# SWM341_DAPLink_2T45.net
KiCad netlist of a schematic drawn in EasyEDA
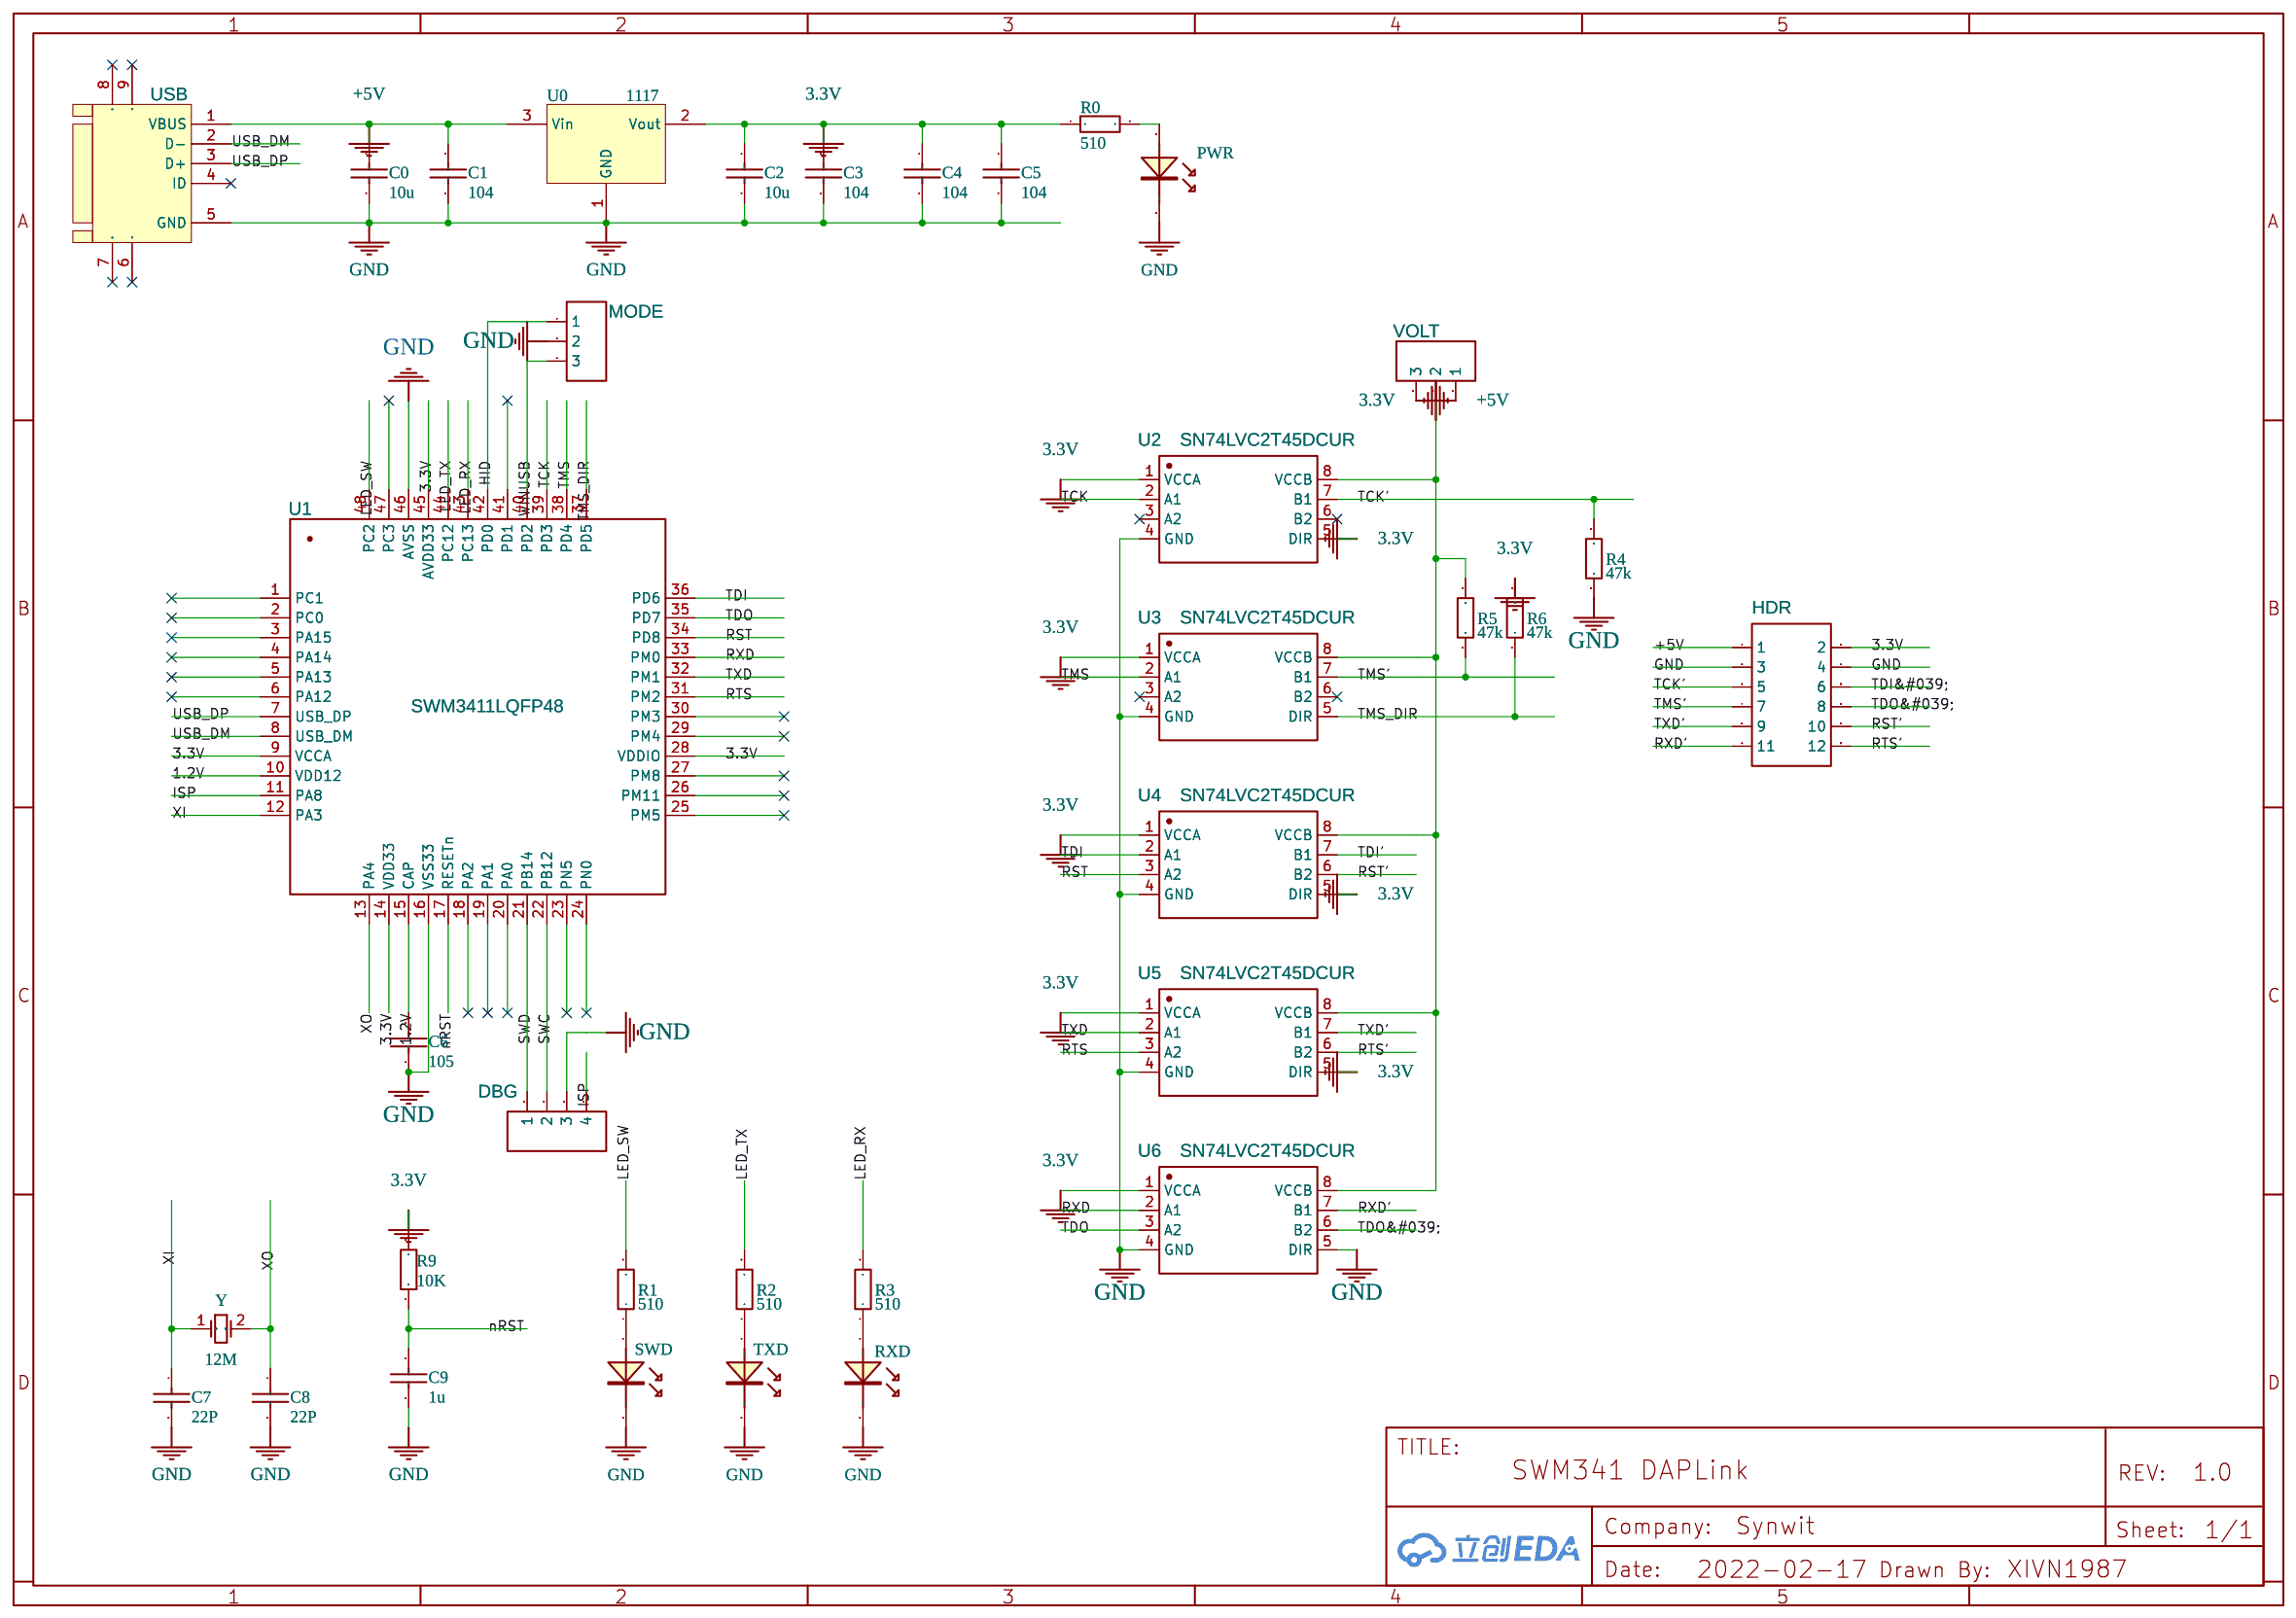
[diagram p0: schematic sheet]

(export (version "E")
  (design (tool "Eeschema 10.0.6"))
  (components
    (comp (ref "C0") (value "10u") (libsource (lib "") (part "Unknown_180_-740")))
    (comp (ref "C1") (value "104") (libsource (lib "") (part "Unknown_220_-740")))
    (comp (ref "C2") (value "10u") (libsource (lib "") (part "Unknown_370_-740")))
    (comp (ref "C3") (value "104") (libsource (lib "") (part "Unknown_410_-740")))
    (comp (ref "C4") (value "104") (libsource (lib "") (part "Unknown_460_-740")))
    (comp (ref "C5") (value "104") (libsource (lib "") (part "Unknown_500_-740")))
    (comp (ref "C6") (value "105") (libsource (lib "") (part "Unknown_200_-300")))
    (comp (ref "C7") (value "22P") (libsource (lib "") (part "Unknown_80_-120")))
    (comp (ref "C8") (value "22P") (libsource (lib "") (part "Unknown_130_-120")))
    (comp (ref "C9") (value "1u") (libsource (lib "") (part "Unknown_200_-130")))
    (comp (ref "DBG")
      (value "HDR-M-2.54_1x4")
      (fields (field (name "BOM_Supplier Part") "C124378"))
      (libsource (lib "") (part "HDR-M-2.54_1x4"))
    )
    (comp (ref "HDR")
      (value "HDR-M-2.54_2x6")
      (fields (field (name "BOM_Supplier Part") "C124388"))
      (libsource (lib "") (part "HDR-M-2.54_2x6"))
    )
    (comp (ref "MODE")
      (value "HDR-M-2.54_1x3")
      (fields (field (name "BOM_Supplier Part") "C180248"))
      (libsource (lib "") (part "HDR-M-2.54_1x3_1"))
    )
    (comp (ref "PWR") (value "NO") (libsource (lib "") (part "Unknown_580_-750")))
    (comp (ref "R0") (value "510") (libsource (lib "") (part "Unknown_560_-750")))
    (comp (ref "R1") (value "510") (libsource (lib "") (part "Unknown_310_-170")))
    (comp (ref "R2") (value "510") (libsource (lib "") (part "Unknown_370_-170")))
    (comp (ref "R3") (value "510") (libsource (lib "") (part "Unknown_430_-170")))
    (comp (ref "R4") (value "47k") (libsource (lib "") (part "Unknown_800_-540")))
    (comp (ref "R5") (value "47k") (libsource (lib "") (part "Unknown_735_-510")))
    (comp (ref "R6") (value "47k") (libsource (lib "") (part "Unknown_760_-510")))
    (comp (ref "R9") (value "10K") (libsource (lib "") (part "Unknown_200_-180")))
    (comp (ref "RXD") (value "NO") (libsource (lib "") (part "Unknown_430_-140")))
    (comp (ref "SWD") (value "NO") (libsource (lib "") (part "Unknown_310_-140")))
    (comp (ref "TXD") (value "NO") (libsource (lib "") (part "Unknown_370_-140")))
    (comp (ref "U0") (value "1117") (libsource (lib "") (part "Unknown_330_-720")))
    (comp (ref "U1") (value "SWM3411LQFP48") (libsource (lib "") (part "SWM3411LQFP48")))
    (comp (ref "U2")
      (value "SN74LVC2T45DCUR")
      (fields (field (name "BOM_Supplier Part") "C15741"))
      (libsource (lib "") (part "SN74LVC2T45DCUR"))
    )
    (comp (ref "U3")
      (value "SN74LVC2T45DCUR")
      (fields (field (name "BOM_Supplier Part") "C15741"))
      (libsource (lib "") (part "SN74LVC2T45DCUR"))
    )
    (comp (ref "U4")
      (value "SN74LVC2T45DCUR")
      (fields (field (name "BOM_Supplier Part") "C15741"))
      (libsource (lib "") (part "SN74LVC2T45DCUR"))
    )
    (comp (ref "U5")
      (value "SN74LVC2T45DCUR")
      (fields (field (name "BOM_Supplier Part") "C15741"))
      (libsource (lib "") (part "SN74LVC2T45DCUR"))
    )
    (comp (ref "U6")
      (value "SN74LVC2T45DCUR")
      (fields (field (name "BOM_Supplier Part") "C15741"))
      (libsource (lib "") (part "SN74LVC2T45DCUR"))
    )
    (comp (ref "USB") (value "MicroUSB") (libsource (lib "") (part "MicroUSB")))
    (comp (ref "VOLT")
      (value "HDR-M-2.54_1x3")
      (fields (field (name "BOM_Supplier Part") "C180248"))
      (libsource (lib "") (part "HDR-M-2.54_1x3"))
    )
    (comp (ref "Y") (value "12M") (libsource (lib "") (part "Unknown_100_-140")))
  )
  (nets
    (net (code "1") (name "+5V") (class "Default")
      (node (ref "C0") (pin "1") (pinfunction "1_1") (pintype "unspecified"))
      (node (ref "C1") (pin "1") (pinfunction "1_1") (pintype "unspecified"))
      (node (ref "HDR") (pin "1") (pinfunction "1_1") (pintype "unspecified"))
      (node (ref "U0") (pin "3") (pinfunction "Vin_3") (pintype "unspecified"))
      (node (ref "USB") (pin "1") (pinfunction "VBUS_1") (pintype "unspecified"))
      (node (ref "VOLT") (pin "1") (pinfunction "1_1") (pintype "input"))
    )
    (net (code "2") (name "/1.2V") (class "Default")
      (node (ref "C6") (pin "1") (pinfunction "1_1") (pintype "unspecified"))
      (node (ref "U1") (pin "10") (pinfunction "VDD12_10") (pintype "unspecified"))
      (node (ref "U1") (pin "15") (pinfunction "CAP_15") (pintype "unspecified"))
    )
    (net (code "3") (name "/HID") (class "Default")
      (node (ref "MODE") (pin "1") (pinfunction "1_1") (pintype "input"))
      (node (ref "U1") (pin "42") (pinfunction "PD0_42") (pintype "unspecified"))
    )
    (net (code "4") (name "/ISP") (class "Default")
      (node (ref "DBG") (pin "4") (pinfunction "4_4") (pintype "unspecified"))
      (node (ref "U1") (pin "11") (pinfunction "PA8_11") (pintype "unspecified"))
    )
    (net (code "5") (name "/LED_RX") (class "Default")
      (node (ref "R3") (pin "2") (pinfunction "2_2") (pintype "unspecified"))
      (node (ref "U1") (pin "43") (pinfunction "PC13_43") (pintype "unspecified"))
    )
    (net (code "6") (name "/LED_SW") (class "Default")
      (node (ref "R1") (pin "2") (pinfunction "2_2") (pintype "unspecified"))
      (node (ref "U1") (pin "48") (pinfunction "PC2_48") (pintype "unspecified"))
    )
    (net (code "7") (name "/LED_TX") (class "Default")
      (node (ref "R2") (pin "2") (pinfunction "2_2") (pintype "unspecified"))
      (node (ref "U1") (pin "44") (pinfunction "PC12_44") (pintype "unspecified"))
    )
    (net (code "8") (name "/RST") (class "Default")
      (node (ref "U1") (pin "34") (pinfunction "PD8_34") (pintype "unspecified"))
      (node (ref "U4") (pin "3") (pinfunction "A2_3") (pintype "unspecified"))
    )
    (net (code "9") (name "/RST'") (class "Default")
      (node (ref "HDR") (pin "10") (pinfunction "10_10") (pintype "unspecified"))
      (node (ref "U4") (pin "6") (pinfunction "B2_6") (pintype "unspecified"))
    )
    (net (code "10") (name "/RTS") (class "Default")
      (node (ref "U1") (pin "31") (pinfunction "PM2_31") (pintype "unspecified"))
      (node (ref "U5") (pin "3") (pinfunction "A2_3") (pintype "unspecified"))
    )
    (net (code "11") (name "/RTS'") (class "Default")
      (node (ref "HDR") (pin "12") (pinfunction "12_12") (pintype "unspecified"))
      (node (ref "U5") (pin "6") (pinfunction "B2_6") (pintype "unspecified"))
    )
    (net (code "12") (name "/RXD") (class "Default")
      (node (ref "U1") (pin "33") (pinfunction "PM0_33") (pintype "unspecified"))
      (node (ref "U6") (pin "2") (pinfunction "A1_2") (pintype "unspecified"))
    )
    (net (code "13") (name "/RXD'") (class "Default")
      (node (ref "HDR") (pin "11") (pinfunction "11_11") (pintype "unspecified"))
      (node (ref "U6") (pin "7") (pinfunction "B1_7") (pintype "unspecified"))
    )
    (net (code "14") (name "/SWC") (class "Default")
      (node (ref "DBG") (pin "2") (pinfunction "2_2") (pintype "unspecified"))
      (node (ref "U1") (pin "22") (pinfunction "PB12_22") (pintype "unspecified"))
    )
    (net (code "15") (name "/SWD") (class "Default")
      (node (ref "DBG") (pin "1") (pinfunction "1_1") (pintype "unspecified"))
      (node (ref "U1") (pin "21") (pinfunction "PB14_21") (pintype "unspecified"))
    )
    (net (code "16") (name "/TCK") (class "Default")
      (node (ref "U1") (pin "39") (pinfunction "PD3_39") (pintype "unspecified"))
      (node (ref "U2") (pin "2") (pinfunction "A1_2") (pintype "unspecified"))
    )
    (net (code "17") (name "/TCK'") (class "Default")
      (node (ref "HDR") (pin "5") (pinfunction "5_5") (pintype "unspecified"))
      (node (ref "R4") (pin "2") (pinfunction "2_2") (pintype "unspecified"))
      (node (ref "U2") (pin "7") (pinfunction "B1_7") (pintype "unspecified"))
    )
    (net (code "18") (name "/TDI") (class "Default")
      (node (ref "U1") (pin "36") (pinfunction "PD6_36") (pintype "unspecified"))
      (node (ref "U4") (pin "2") (pinfunction "A1_2") (pintype "unspecified"))
    )
    (net (code "19") (name "/TDI&#039;") (class "Default")
      (node (ref "HDR") (pin "6") (pinfunction "6_6") (pintype "unspecified"))
    )
    (net (code "20") (name "/TDI'") (class "Default")
      (node (ref "U4") (pin "7") (pinfunction "B1_7") (pintype "unspecified"))
    )
    (net (code "21") (name "/TDO") (class "Default")
      (node (ref "U1") (pin "35") (pinfunction "PD7_35") (pintype "unspecified"))
      (node (ref "U6") (pin "3") (pinfunction "A2_3") (pintype "unspecified"))
    )
    (net (code "22") (name "/TDO&#039;") (class "Default")
      (node (ref "HDR") (pin "8") (pinfunction "8_8") (pintype "unspecified"))
      (node (ref "U6") (pin "6") (pinfunction "B2_6") (pintype "unspecified"))
    )
    (net (code "23") (name "/TMS") (class "Default")
      (node (ref "U1") (pin "38") (pinfunction "PD4_38") (pintype "unspecified"))
      (node (ref "U3") (pin "2") (pinfunction "A1_2") (pintype "unspecified"))
    )
    (net (code "24") (name "/TMS'") (class "Default")
      (node (ref "HDR") (pin "7") (pinfunction "7_7") (pintype "unspecified"))
      (node (ref "R5") (pin "1") (pinfunction "1_1") (pintype "unspecified"))
      (node (ref "U3") (pin "7") (pinfunction "B1_7") (pintype "unspecified"))
    )
    (net (code "25") (name "/TMS_DIR") (class "Default")
      (node (ref "R6") (pin "1") (pinfunction "1_1") (pintype "unspecified"))
      (node (ref "U1") (pin "37") (pinfunction "PD5_37") (pintype "unspecified"))
      (node (ref "U3") (pin "5") (pinfunction "DIR_5") (pintype "unspecified"))
    )
    (net (code "26") (name "/TXD") (class "Default")
      (node (ref "U1") (pin "32") (pinfunction "PM1_32") (pintype "unspecified"))
      (node (ref "U5") (pin "2") (pinfunction "A1_2") (pintype "unspecified"))
    )
    (net (code "27") (name "/TXD'") (class "Default")
      (node (ref "HDR") (pin "9") (pinfunction "9_9") (pintype "unspecified"))
      (node (ref "U5") (pin "7") (pinfunction "B1_7") (pintype "unspecified"))
    )
    (net (code "28") (name "/USB_DM") (class "Default")
      (node (ref "U1") (pin "8") (pinfunction "USB_DM_8") (pintype "unspecified"))
      (node (ref "USB") (pin "2") (pinfunction "D-_2") (pintype "unspecified"))
    )
    (net (code "29") (name "/USB_DP") (class "Default")
      (node (ref "U1") (pin "7") (pinfunction "USB_DP_7") (pintype "unspecified"))
      (node (ref "USB") (pin "3") (pinfunction "D+_3") (pintype "unspecified"))
    )
    (net (code "30") (name "/WINUSB") (class "Default")
      (node (ref "MODE") (pin "3") (pinfunction "3_3") (pintype "input"))
      (node (ref "U1") (pin "40") (pinfunction "PD2_40") (pintype "unspecified"))
    )
    (net (code "31") (name "/XI") (class "Default")
      (node (ref "C7") (pin "1") (pinfunction "1_1") (pintype "unspecified"))
      (node (ref "U1") (pin "12") (pinfunction "PA3_12") (pintype "unspecified"))
      (node (ref "Y") (pin "1") (pinfunction "OSC1_1") (pintype "unspecified"))
    )
    (net (code "32") (name "/XO") (class "Default")
      (node (ref "C8") (pin "1") (pinfunction "1_1") (pintype "unspecified"))
      (node (ref "U1") (pin "13") (pinfunction "PA4_13") (pintype "unspecified"))
      (node (ref "Y") (pin "2") (pinfunction "OSC2_2") (pintype "unspecified"))
    )
    (net (code "33") (name "/nRST") (class "Default")
      (node (ref "C9") (pin "1") (pinfunction "1_1") (pintype "unspecified"))
      (node (ref "R9") (pin "1") (pinfunction "1_1") (pintype "unspecified"))
      (node (ref "U1") (pin "17") (pinfunction "RESETn_17") (pintype "unspecified"))
    )
    (net (code "34") (name "3.3V") (class "Default")
      (node (ref "C2") (pin "1") (pinfunction "1_1") (pintype "unspecified"))
      (node (ref "C3") (pin "1") (pinfunction "1_1") (pintype "unspecified"))
      (node (ref "C4") (pin "1") (pinfunction "1_1") (pintype "unspecified"))
      (node (ref "C5") (pin "1") (pinfunction "1_1") (pintype "unspecified"))
      (node (ref "HDR") (pin "2") (pinfunction "2_2") (pintype "unspecified"))
      (node (ref "R0") (pin "1") (pinfunction "1_1") (pintype "unspecified"))
      (node (ref "R6") (pin "2") (pinfunction "2_2") (pintype "unspecified"))
      (node (ref "R9") (pin "2") (pinfunction "2_2") (pintype "unspecified"))
      (node (ref "U0") (pin "2") (pinfunction "Vout_2") (pintype "unspecified"))
      (node (ref "U1") (pin "14") (pinfunction "VDD33_14") (pintype "unspecified"))
      (node (ref "U1") (pin "28") (pinfunction "VDDIO_28") (pintype "unspecified"))
      (node (ref "U1") (pin "45") (pinfunction "AVDD33_45") (pintype "unspecified"))
      (node (ref "U1") (pin "9") (pinfunction "VCCA_9") (pintype "unspecified"))
      (node (ref "U2") (pin "1") (pinfunction "VCCA_1") (pintype "unspecified"))
      (node (ref "U2") (pin "5") (pinfunction "DIR_5") (pintype "unspecified"))
      (node (ref "U3") (pin "1") (pinfunction "VCCA_1") (pintype "unspecified"))
      (node (ref "U4") (pin "1") (pinfunction "VCCA_1") (pintype "unspecified"))
      (node (ref "U4") (pin "5") (pinfunction "DIR_5") (pintype "unspecified"))
      (node (ref "U5") (pin "1") (pinfunction "VCCA_1") (pintype "unspecified"))
      (node (ref "U5") (pin "5") (pinfunction "DIR_5") (pintype "unspecified"))
      (node (ref "U6") (pin "1") (pinfunction "VCCA_1") (pintype "unspecified"))
      (node (ref "VOLT") (pin "3") (pinfunction "3_3") (pintype "input"))
    )
    (net (code "35") (name "GND") (class "Default")
      (node (ref "C0") (pin "2") (pinfunction "2_2") (pintype "unspecified"))
      (node (ref "C1") (pin "2") (pinfunction "2_2") (pintype "unspecified"))
      (node (ref "C2") (pin "2") (pinfunction "2_2") (pintype "unspecified"))
      (node (ref "C3") (pin "2") (pinfunction "2_2") (pintype "unspecified"))
      (node (ref "C4") (pin "2") (pinfunction "2_2") (pintype "unspecified"))
      (node (ref "C5") (pin "2") (pinfunction "2_2") (pintype "unspecified"))
      (node (ref "C6") (pin "2") (pinfunction "2_2") (pintype "unspecified"))
      (node (ref "C7") (pin "2") (pinfunction "2_2") (pintype "unspecified"))
      (node (ref "C8") (pin "2") (pinfunction "2_2") (pintype "unspecified"))
      (node (ref "C9") (pin "2") (pinfunction "2_2") (pintype "unspecified"))
      (node (ref "DBG") (pin "3") (pinfunction "3_3") (pintype "unspecified"))
      (node (ref "HDR") (pin "3") (pinfunction "3_3") (pintype "unspecified"))
      (node (ref "HDR") (pin "4") (pinfunction "4_4") (pintype "unspecified"))
      (node (ref "MODE") (pin "2") (pinfunction "2_2") (pintype "input"))
      (node (ref "PWR") (pin "2") (pinfunction "K_2") (pintype "unspecified"))
      (node (ref "R4") (pin "1") (pinfunction "1_1") (pintype "unspecified"))
      (node (ref "RXD") (pin "2") (pinfunction "K_2") (pintype "unspecified"))
      (node (ref "SWD") (pin "2") (pinfunction "K_2") (pintype "unspecified"))
      (node (ref "TXD") (pin "2") (pinfunction "K_2") (pintype "unspecified"))
      (node (ref "U0") (pin "1") (pinfunction "GND_1") (pintype "unspecified"))
      (node (ref "U1") (pin "16") (pinfunction "VSS33_16") (pintype "unspecified"))
      (node (ref "U1") (pin "46") (pinfunction "AVSS_46") (pintype "unspecified"))
      (node (ref "U2") (pin "4") (pinfunction "GND_4") (pintype "unspecified"))
      (node (ref "U3") (pin "4") (pinfunction "GND_4") (pintype "unspecified"))
      (node (ref "U4") (pin "4") (pinfunction "GND_4") (pintype "unspecified"))
      (node (ref "U5") (pin "4") (pinfunction "GND_4") (pintype "unspecified"))
      (node (ref "U6") (pin "4") (pinfunction "GND_4") (pintype "unspecified"))
      (node (ref "U6") (pin "5") (pinfunction "DIR_5") (pintype "unspecified"))
      (node (ref "USB") (pin "5") (pinfunction "GND_5") (pintype "unspecified"))
    )
    (net (code "36") (name "Net-(PWR-A)") (class "Default")
      (node (ref "PWR") (pin "1") (pinfunction "A_1") (pintype "unspecified"))
      (node (ref "R0") (pin "2") (pinfunction "2_2") (pintype "unspecified"))
    )
    (net (code "37") (name "Net-(RXD-A)") (class "Default")
      (node (ref "R3") (pin "1") (pinfunction "1_1") (pintype "unspecified"))
      (node (ref "RXD") (pin "1") (pinfunction "A_1") (pintype "unspecified"))
    )
    (net (code "38") (name "Net-(SWD-A)") (class "Default")
      (node (ref "R1") (pin "1") (pinfunction "1_1") (pintype "unspecified"))
      (node (ref "SWD") (pin "1") (pinfunction "A_1") (pintype "unspecified"))
    )
    (net (code "39") (name "Net-(TXD-A)") (class "Default")
      (node (ref "R2") (pin "1") (pinfunction "1_1") (pintype "unspecified"))
      (node (ref "TXD") (pin "1") (pinfunction "A_1") (pintype "unspecified"))
    )
    (net (code "40") (name "Net-(U2-VCCB)") (class "Default")
      (node (ref "R5") (pin "2") (pinfunction "2_2") (pintype "unspecified"))
      (node (ref "U2") (pin "8") (pinfunction "VCCB_8") (pintype "unspecified"))
      (node (ref "U3") (pin "8") (pinfunction "VCCB_8") (pintype "unspecified"))
      (node (ref "U4") (pin "8") (pinfunction "VCCB_8") (pintype "unspecified"))
      (node (ref "U5") (pin "8") (pinfunction "VCCB_8") (pintype "unspecified"))
      (node (ref "U6") (pin "8") (pinfunction "VCCB_8") (pintype "unspecified"))
      (node (ref "VOLT") (pin "2") (pinfunction "2_2") (pintype "input"))
    )
    (net (code "41") (name "unconnected-(U1-PA0-Pad20)") (class "Default")
      (node (ref "U1") (pin "20") (pinfunction "PA0_20") (pintype "unspecified+no_connect"))
    )
    (net (code "42") (name "unconnected-(U1-PA1-Pad19)") (class "Default")
      (node (ref "U1") (pin "19") (pinfunction "PA1_19") (pintype "unspecified+no_connect"))
    )
    (net (code "43") (name "unconnected-(U1-PA2-Pad18)") (class "Default")
      (node (ref "U1") (pin "18") (pinfunction "PA2_18") (pintype "unspecified+no_connect"))
    )
    (net (code "44") (name "unconnected-(U1-PA12-Pad6)") (class "Default")
      (node (ref "U1") (pin "6") (pinfunction "PA12_6") (pintype "unspecified+no_connect"))
    )
    (net (code "45") (name "unconnected-(U1-PA13-Pad5)") (class "Default")
      (node (ref "U1") (pin "5") (pinfunction "PA13_5") (pintype "unspecified+no_connect"))
    )
    (net (code "46") (name "unconnected-(U1-PA14-Pad4)") (class "Default")
      (node (ref "U1") (pin "4") (pinfunction "PA14_4") (pintype "unspecified+no_connect"))
    )
    (net (code "47") (name "unconnected-(U1-PA15-Pad3)") (class "Default")
      (node (ref "U1") (pin "3") (pinfunction "PA15_3") (pintype "unspecified+no_connect"))
    )
    (net (code "48") (name "unconnected-(U1-PC0-Pad2)") (class "Default")
      (node (ref "U1") (pin "2") (pinfunction "PC0_2") (pintype "unspecified+no_connect"))
    )
    (net (code "49") (name "unconnected-(U1-PC1-Pad1)") (class "Default")
      (node (ref "U1") (pin "1") (pinfunction "PC1_1") (pintype "unspecified+no_connect"))
    )
    (net (code "50") (name "unconnected-(U1-PC3-Pad47)") (class "Default")
      (node (ref "U1") (pin "47") (pinfunction "PC3_47") (pintype "unspecified+no_connect"))
    )
    (net (code "51") (name "unconnected-(U1-PD1-Pad41)") (class "Default")
      (node (ref "U1") (pin "41") (pinfunction "PD1_41") (pintype "unspecified+no_connect"))
    )
    (net (code "52") (name "unconnected-(U1-PM3-Pad30)") (class "Default")
      (node (ref "U1") (pin "30") (pinfunction "PM3_30") (pintype "unspecified+no_connect"))
    )
    (net (code "53") (name "unconnected-(U1-PM4-Pad29)") (class "Default")
      (node (ref "U1") (pin "29") (pinfunction "PM4_29") (pintype "unspecified+no_connect"))
    )
    (net (code "54") (name "unconnected-(U1-PM5-Pad25)") (class "Default")
      (node (ref "U1") (pin "25") (pinfunction "PM5_25") (pintype "unspecified+no_connect"))
    )
    (net (code "55") (name "unconnected-(U1-PM8-Pad27)") (class "Default")
      (node (ref "U1") (pin "27") (pinfunction "PM8_27") (pintype "unspecified+no_connect"))
    )
    (net (code "56") (name "unconnected-(U1-PM11-Pad26)") (class "Default")
      (node (ref "U1") (pin "26") (pinfunction "PM11_26") (pintype "unspecified+no_connect"))
    )
    (net (code "57") (name "unconnected-(U1-PN0-Pad24)") (class "Default")
      (node (ref "U1") (pin "24") (pinfunction "PN0_24") (pintype "unspecified+no_connect"))
    )
    (net (code "58") (name "unconnected-(U1-PN5-Pad23)") (class "Default")
      (node (ref "U1") (pin "23") (pinfunction "PN5_23") (pintype "unspecified+no_connect"))
    )
    (net (code "59") (name "unconnected-(U2-A2-Pad3)") (class "Default")
      (node (ref "U2") (pin "3") (pinfunction "A2_3") (pintype "unspecified+no_connect"))
    )
    (net (code "60") (name "unconnected-(U2-B2-Pad6)") (class "Default")
      (node (ref "U2") (pin "6") (pinfunction "B2_6") (pintype "unspecified+no_connect"))
    )
    (net (code "61") (name "unconnected-(U3-A2-Pad3)") (class "Default")
      (node (ref "U3") (pin "3") (pinfunction "A2_3") (pintype "unspecified+no_connect"))
    )
    (net (code "62") (name "unconnected-(U3-B2-Pad6)") (class "Default")
      (node (ref "U3") (pin "6") (pinfunction "B2_6") (pintype "unspecified+no_connect"))
    )
    (net (code "63") (name "unconnected-(USB-ID-Pad4)") (class "Default")
      (node (ref "USB") (pin "4") (pinfunction "ID_4") (pintype "unspecified+no_connect"))
    )
    (net (code "64") (name "unconnected-(USB-NC-Pad6)") (class "Default")
      (node (ref "USB") (pin "6") (pinfunction "NC_6") (pintype "unspecified+no_connect"))
    )
    (net (code "65") (name "unconnected-(USB-NC-Pad7)") (class "Default")
      (node (ref "USB") (pin "7") (pinfunction "NC_7") (pintype "unspecified+no_connect"))
    )
    (net (code "66") (name "unconnected-(USB-NC-Pad8)") (class "Default")
      (node (ref "USB") (pin "8") (pinfunction "NC_8") (pintype "unspecified+no_connect"))
    )
    (net (code "67") (name "unconnected-(USB-NC-Pad9)") (class "Default")
      (node (ref "USB") (pin "9") (pinfunction "NC_9") (pintype "unspecified+no_connect"))
    )
  )
)
